# TF.net
KiCad netlist of a schematic drawn in Altium Designer
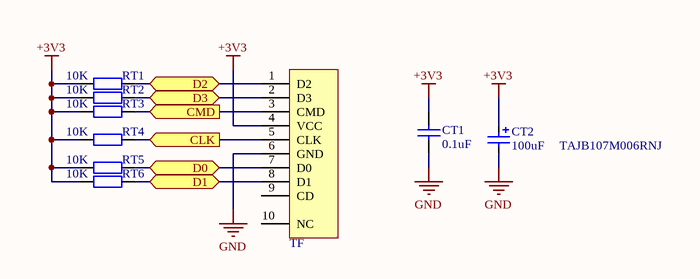
[diagram p0: TF.SchDoc]

(export (version "E")
  (design (tool "Eeschema 10.0.6"))
  (components
    (comp (ref "CT1")
      (value "0.1uF")
      (footprint "CAPC1608N")
      (description "Capacitor")
      (fields (field (name "Comment") "Cap1") (field (name "PUBLISHER") "Altium Limited"))
      (libsource (lib "Peace的集成库") (part "Cap1"))
    )
    (comp (ref "CT2")
      (value "100uF     TAJB107M006RNJ")
      (footprint "CAP_TAN_B_3518")
      (description "Capacitor")
      (fields (field (name "Comment") "Cap_Tan"))
      (libsource (lib "Peace的集成库") (part "Cap_Tan"))
    )
    (comp (ref "RT1")
      (value "10K")
      (footprint "RESC1608N")
      (description "Resistor")
      (fields (field (name "Comment") "Res1") (field (name "PUBLISHER") "Altium Limited"))
      (libsource (lib "Peace的集成库") (part "Res1"))
    )
    (comp (ref "RT2")
      (value "10K")
      (footprint "RESC1608N")
      (description "Resistor")
      (fields (field (name "Comment") "Res1") (field (name "PUBLISHER") "Altium Limited"))
      (libsource (lib "Peace的集成库") (part "Res1"))
    )
    (comp (ref "RT3")
      (value "10K")
      (footprint "RESC1608N")
      (description "Resistor")
      (fields (field (name "Comment") "Res1") (field (name "PUBLISHER") "Altium Limited"))
      (libsource (lib "Peace的集成库") (part "Res1"))
    )
    (comp (ref "RT4")
      (value "10K")
      (footprint "RESC1608N")
      (description "Resistor")
      (fields (field (name "Comment") "Res1") (field (name "PUBLISHER") "Altium Limited"))
      (libsource (lib "Peace的集成库") (part "Res1"))
    )
    (comp (ref "RT5")
      (value "10K")
      (footprint "RESC1608N")
      (description "Resistor")
      (fields (field (name "Comment") "Res1") (field (name "PUBLISHER") "Altium Limited"))
      (libsource (lib "Peace的集成库") (part "Res1"))
    )
    (comp (ref "RT6")
      (value "10K")
      (footprint "RESC1608N")
      (description "Resistor")
      (fields (field (name "Comment") "Res1") (field (name "PUBLISHER") "Altium Limited"))
      (libsource (lib "Peace的集成库") (part "Res1"))
    )
    (comp (ref "TF") (value "TF") (footprint "TF-2") (libsource (lib "Peace的集成库") (part "TF2")))
  )
  (nets
    (net (code "1") (name "+3V3") (class "Default")
      (node (ref "CT1") (pin "2") (pinfunction "2_2") (pintype "passive"))
      (node (ref "CT2") (pin "1") (pinfunction "1_1") (pintype "passive"))
      (node (ref "RT1") (pin "1") (pinfunction "1_1") (pintype "passive"))
      (node (ref "RT2") (pin "1") (pinfunction "1_1") (pintype "passive"))
      (node (ref "RT3") (pin "1") (pinfunction "1_1") (pintype "passive"))
      (node (ref "RT4") (pin "1") (pinfunction "1_1") (pintype "passive"))
      (node (ref "RT5") (pin "1") (pinfunction "1_1") (pintype "passive"))
      (node (ref "RT6") (pin "1") (pinfunction "1_1") (pintype "passive"))
      (node (ref "TF") (pin "4") (pinfunction "VCC_4") (pintype "passive"))
    )
    (net (code "2") (name "/CLK") (class "Default")
      (node (ref "RT4") (pin "2") (pinfunction "2_2") (pintype "passive"))
      (node (ref "TF") (pin "5") (pinfunction "CLK_5") (pintype "passive"))
    )
    (net (code "3") (name "/CMD") (class "Default")
      (node (ref "RT3") (pin "2") (pinfunction "2_2") (pintype "passive"))
      (node (ref "TF") (pin "3") (pinfunction "CMD_3") (pintype "passive"))
    )
    (net (code "4") (name "/D0") (class "Default")
      (node (ref "RT5") (pin "2") (pinfunction "2_2") (pintype "passive"))
      (node (ref "TF") (pin "7") (pinfunction "D0_7") (pintype "passive"))
    )
    (net (code "5") (name "/D1") (class "Default")
      (node (ref "RT6") (pin "2") (pinfunction "2_2") (pintype "passive"))
      (node (ref "TF") (pin "8") (pinfunction "D1_8") (pintype "passive"))
    )
    (net (code "6") (name "/D2") (class "Default")
      (node (ref "RT1") (pin "2") (pinfunction "2_2") (pintype "passive"))
      (node (ref "TF") (pin "1") (pinfunction "D2_1") (pintype "passive"))
    )
    (net (code "7") (name "/D3") (class "Default")
      (node (ref "RT2") (pin "2") (pinfunction "2_2") (pintype "passive"))
      (node (ref "TF") (pin "2") (pinfunction "D3_2") (pintype "passive"))
    )
    (net (code "8") (name "GND") (class "Default")
      (node (ref "CT1") (pin "1") (pinfunction "1_1") (pintype "passive"))
      (node (ref "CT2") (pin "2") (pinfunction "2_2") (pintype "passive"))
      (node (ref "TF") (pin "6") (pinfunction "GND_6") (pintype "passive"))
    )
    (net (code "9") (name "unconnected-(TF-CD-Pad9)") (class "Default")
      (node (ref "TF") (pin "9") (pinfunction "CD_9") (pintype "passive"))
    )
    (net (code "10") (name "unconnected-(TF-NC-Pad10)") (class "Default")
      (node (ref "TF") (pin "10") (pinfunction "NC_10") (pintype "passive"))
    )
  )
)
